# introAu.net
KiCad netlist of a schematic drawn in EAGLE
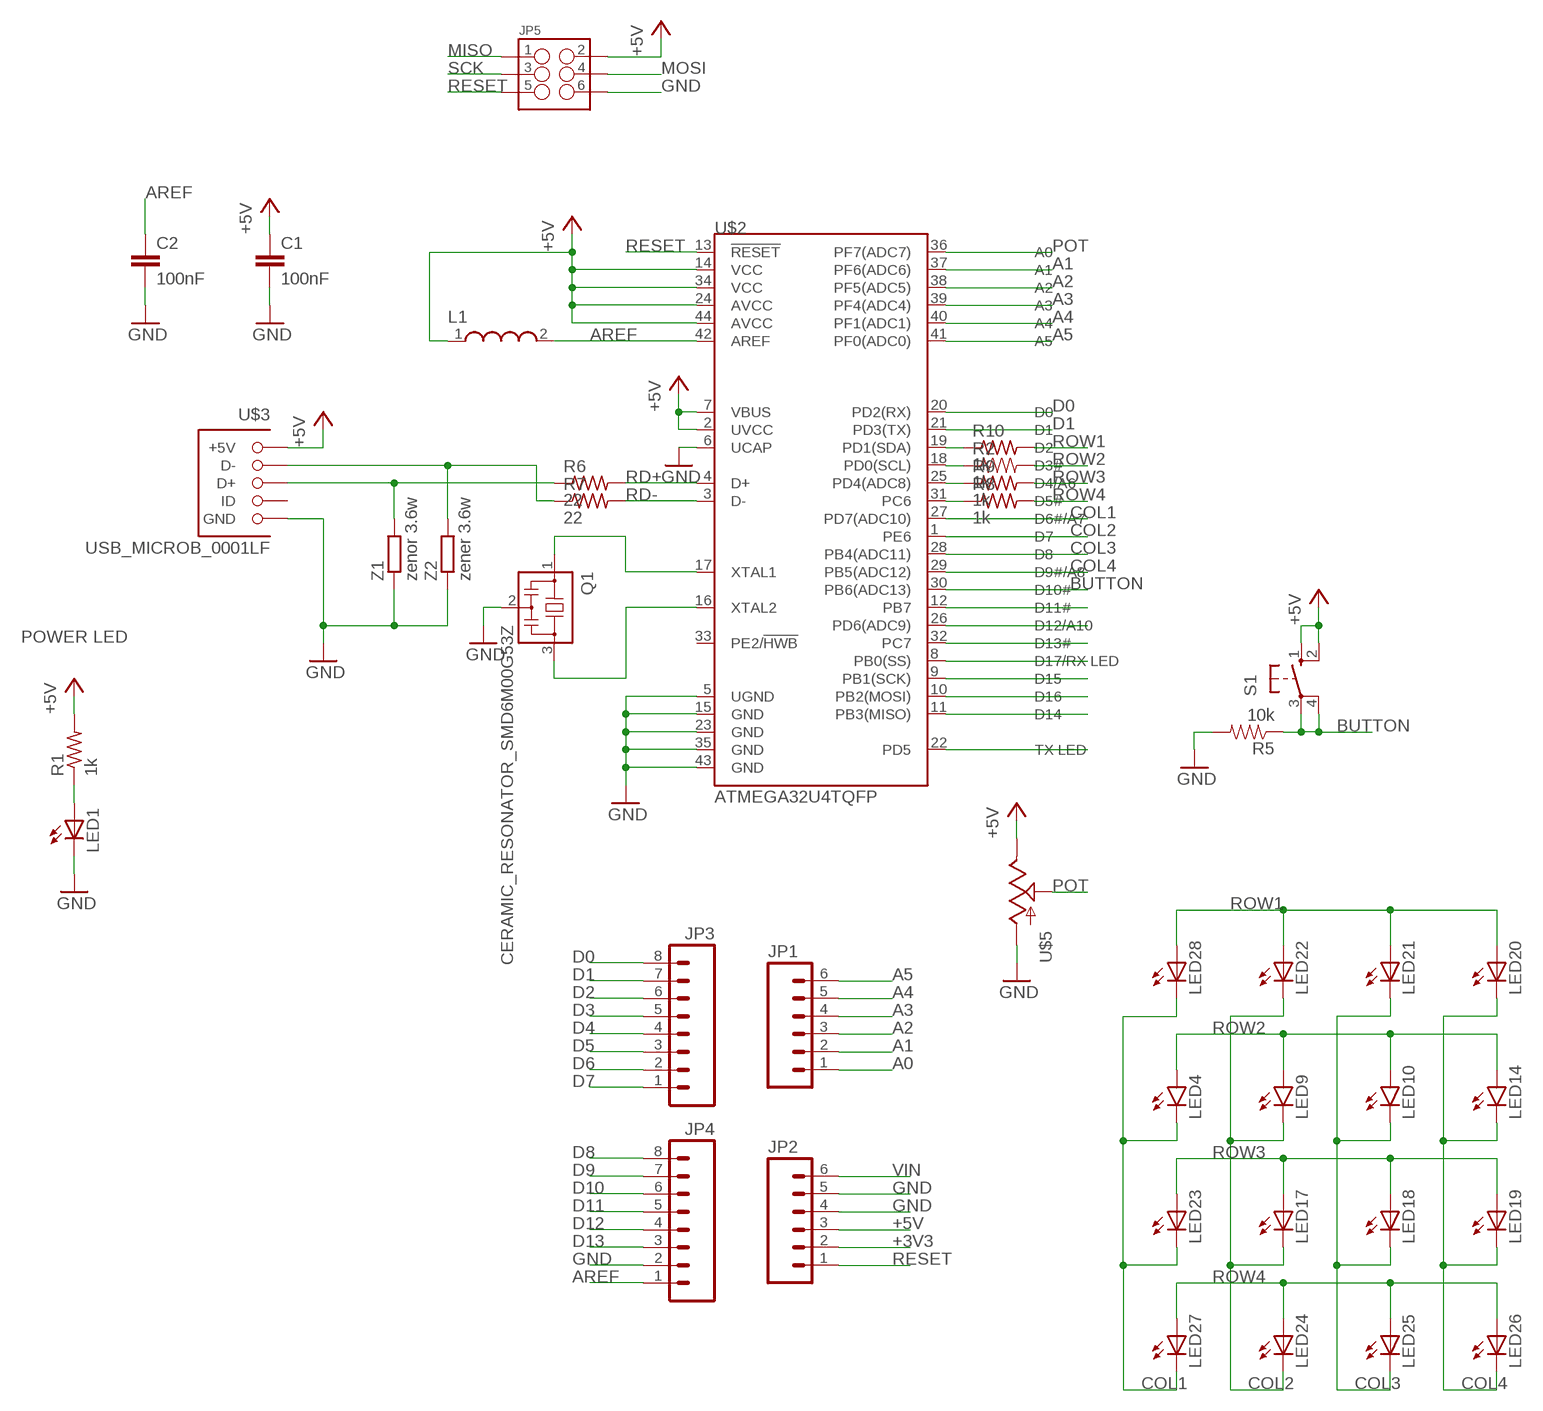
[diagram p0: schematic, sheet 1]

(export (version "E")
  (design (tool "Eeschema 10.0.6"))
  (components
    (comp (ref "C1")
      (value "100nF")
      (footprint "eagle-import:C0805")
      (libsource (lib "eagle-import") (part "C-EUC0805"))
    )
    (comp (ref "C2")
      (value "100nF")
      (footprint "eagle-import:C0805")
      (libsource (lib "eagle-import") (part "C-EUC0805"))
    )
    (comp (ref "JP1")
      (value "M06SMD-STRAIGHT-COMBO")
      (footprint "eagle-import:1X06_SMD_STRAIGHT_COMBO")
      (libsource (lib "eagle-import") (part "M06SMD-STRAIGHT-COMBO"))
    )
    (comp (ref "JP2")
      (value "M06SMD-STRAIGHT-COMBO")
      (footprint "eagle-import:1X06_SMD_STRAIGHT_COMBO")
      (libsource (lib "eagle-import") (part "M06SMD-STRAIGHT-COMBO"))
    )
    (comp (ref "JP3")
      (value "M08SMD-COMBO")
      (footprint "eagle-import:1X08_SMD_COMBINED")
      (libsource (lib "eagle-import") (part "M08SMD-COMBO"))
    )
    (comp (ref "JP4")
      (value "M08SMD-COMBO")
      (footprint "eagle-import:1X08_SMD_COMBINED")
      (libsource (lib "eagle-import") (part "M08SMD-COMBO"))
    )
    (comp (ref "JP5")
      (value "M03X22X3_SILK_SM")
      (footprint "eagle-import:2X3")
      (libsource (lib "eagle-import") (part "M03X22X3_SILK_SM"))
    )
    (comp (ref "L1")
      (value "WE-CBF_0805(WB/HS)")
      (footprint "eagle-import:WE-CBF_0805(W=3.0)")
      (libsource (lib "eagle-import") (part "WE-CBF_0805(WB/HS)"))
    )
    (comp (ref "LED1")
      (value "LEDCHIPLED_0805")
      (footprint "eagle-import:CHIPLED_0805")
      (libsource (lib "eagle-import") (part "LEDCHIPLED_0805"))
    )
    (comp (ref "LED4")
      (value "LED5MM")
      (footprint "eagle-import:LED5MM")
      (libsource (lib "eagle-import") (part "LED5MM"))
    )
    (comp (ref "LED9")
      (value "LED5MM")
      (footprint "eagle-import:LED5MM")
      (libsource (lib "eagle-import") (part "LED5MM"))
    )
    (comp (ref "LED10")
      (value "LED5MM")
      (footprint "eagle-import:LED5MM")
      (libsource (lib "eagle-import") (part "LED5MM"))
    )
    (comp (ref "LED14")
      (value "LED5MM")
      (footprint "eagle-import:LED5MM")
      (libsource (lib "eagle-import") (part "LED5MM"))
    )
    (comp (ref "LED17")
      (value "LEDCHIPLED_0805")
      (footprint "eagle-import:CHIPLED_0805")
      (libsource (lib "eagle-import") (part "LEDCHIPLED_0805"))
    )
    (comp (ref "LED18")
      (value "LEDCHIPLED_0805")
      (footprint "eagle-import:CHIPLED_0805")
      (libsource (lib "eagle-import") (part "LEDCHIPLED_0805"))
    )
    (comp (ref "LED19")
      (value "LEDCHIPLED_0805")
      (footprint "eagle-import:CHIPLED_0805")
      (libsource (lib "eagle-import") (part "LEDCHIPLED_0805"))
    )
    (comp (ref "LED20")
      (value "LEDCHIPLED_0805")
      (footprint "eagle-import:CHIPLED_0805")
      (libsource (lib "eagle-import") (part "LEDCHIPLED_0805"))
    )
    (comp (ref "LED21")
      (value "LEDCHIPLED_0805")
      (footprint "eagle-import:CHIPLED_0805")
      (libsource (lib "eagle-import") (part "LEDCHIPLED_0805"))
    )
    (comp (ref "LED22")
      (value "LEDCHIPLED_0805")
      (footprint "eagle-import:CHIPLED_0805")
      (libsource (lib "eagle-import") (part "LEDCHIPLED_0805"))
    )
    (comp (ref "LED23")
      (value "LEDCHIPLED_0805")
      (footprint "eagle-import:CHIPLED_0805")
      (libsource (lib "eagle-import") (part "LEDCHIPLED_0805"))
    )
    (comp (ref "LED24")
      (value "LEDCHIPLED_0805")
      (footprint "eagle-import:CHIPLED_0805")
      (libsource (lib "eagle-import") (part "LEDCHIPLED_0805"))
    )
    (comp (ref "LED25")
      (value "LEDCHIPLED_0805")
      (footprint "eagle-import:CHIPLED_0805")
      (libsource (lib "eagle-import") (part "LEDCHIPLED_0805"))
    )
    (comp (ref "LED26")
      (value "LEDCHIPLED_0805")
      (footprint "eagle-import:CHIPLED_0805")
      (libsource (lib "eagle-import") (part "LEDCHIPLED_0805"))
    )
    (comp (ref "LED27")
      (value "LEDCHIPLED_0805")
      (footprint "eagle-import:CHIPLED_0805")
      (libsource (lib "eagle-import") (part "LEDCHIPLED_0805"))
    )
    (comp (ref "LED28")
      (value "LEDCHIPLED_0805")
      (footprint "eagle-import:CHIPLED_0805")
      (libsource (lib "eagle-import") (part "LEDCHIPLED_0805"))
    )
    (comp (ref "Q1")
      (value "CERAMIC_RESONATOR_SMD6M00G53Z")
      (footprint "eagle-import:CERAMIC_RESONATOR_SMD")
      (fields (field (name "MPN") "CSTCR6M00G53-R0"))
      (libsource (lib "eagle-import") (part "CERAMIC_RESONATOR_SMD6M00G53Z"))
    )
    (comp (ref "R1")
      (value "1k")
      (footprint "eagle-import:R0805")
      (libsource (lib "eagle-import") (part "R-US_R0805"))
    )
    (comp (ref "R2")
      (value "1k")
      (footprint "eagle-import:AXIAL-0.3EZ")
      (libsource (lib "eagle-import") (part "1KOHM1/4W5%(PTH)HORIZ-KIT"))
    )
    (comp (ref "R5")
      (value "10k")
      (footprint "eagle-import:AXIAL-0.3EZ")
      (libsource (lib "eagle-import") (part "1KOHM1/4W5%(PTH)HORIZ-KIT"))
    )
    (comp (ref "R6")
      (value "22")
      (footprint "eagle-import:R0805")
      (libsource (lib "eagle-import") (part "R-US_R0805"))
    )
    (comp (ref "R7")
      (value "22")
      (footprint "eagle-import:R0805")
      (libsource (lib "eagle-import") (part "R-US_R0805"))
    )
    (comp (ref "R8")
      (value "1k")
      (footprint "eagle-import:R0805")
      (libsource (lib "eagle-import") (part "R-US_R0805"))
    )
    (comp (ref "R9")
      (value "1k")
      (footprint "eagle-import:R0805")
      (libsource (lib "eagle-import") (part "R-US_R0805"))
    )
    (comp (ref "R10")
      (value "1k")
      (footprint "eagle-import:R0805")
      (libsource (lib "eagle-import") (part "R-US_R0805"))
    )
    (comp (ref "S1")
      (value "TACT_BUTTON")
      (footprint "eagle-import:B3F-10XX")
      (fields (field (name "MPN") "B3F-1000"))
      (libsource (lib "eagle-import") (part "TACT_BUTTON"))
    )
    (comp (ref "U$2")
      (value "ATMEGA32U4TQFP")
      (footprint "eagle-import:SPARKFUN-DIGITALIC_TQFP44")
      (libsource (lib "eagle-import") (part "ATMEGA32U4TQFP"))
    )
    (comp (ref "U$3")
      (value "USB_MICROB_0001LF")
      (footprint "eagle-import:USB_MICROB_CHEAPER")
      (libsource (lib "eagle-import") (part "USB_MICROB_0001LF"))
    )
    (comp (ref "U$5")
      (value "POT")
      (footprint "eagle-import:ALPS_POT")
      (libsource (lib "eagle-import") (part "POT"))
    )
    (comp (ref "Z1")
      (value "zenor 3.6w")
      (footprint "eagle-import:R0603")
      (libsource (lib "eagle-import") (part "R-EU_R0603"))
    )
    (comp (ref "Z2")
      (value "zener 3.6w")
      (footprint "eagle-import:R0603")
      (libsource (lib "eagle-import") (part "R-EU_R0603"))
    )
  )
  (nets
    (net (code "1") (name "+5V") (class "Default")
      (node (ref "C1") (pin "1") (pinfunction "1_1") (pintype "passive"))
      (node (ref "JP2") (pin "3") (pinfunction "3_3") (pintype "passive"))
      (node (ref "JP5") (pin "2") (pinfunction "2_2") (pintype "bidirectional"))
      (node (ref "L1") (pin "1") (pinfunction "1_1") (pintype "passive"))
      (node (ref "R1") (pin "2") (pinfunction "2_2") (pintype "passive"))
      (node (ref "S1") (pin "1") (pinfunction "S_1") (pintype "passive"))
      (node (ref "S1") (pin "2") (pinfunction "S1_2") (pintype "passive"))
      (node (ref "U$2") (pin "14") (pinfunction "VCC_14") (pintype "bidirectional"))
      (node (ref "U$2") (pin "2") (pinfunction "UVCC_2") (pintype "bidirectional"))
      (node (ref "U$2") (pin "24") (pinfunction "AVCC_24") (pintype "bidirectional"))
      (node (ref "U$2") (pin "34") (pinfunction "VCC_34") (pintype "bidirectional"))
      (node (ref "U$2") (pin "44") (pinfunction "AVCC_44") (pintype "bidirectional"))
      (node (ref "U$2") (pin "7") (pinfunction "VBUS_7") (pintype "bidirectional"))
      (node (ref "U$3") (pin "P$1") (pinfunction "+5V_P$1") (pintype "bidirectional"))
      (node (ref "U$5") (pin "P$1") (pinfunction "E_P$1") (pintype "passive"))
    )
    (net (code "2") (name "/+3V3") (class "Default")
      (node (ref "JP2") (pin "2") (pinfunction "2_2") (pintype "passive"))
    )
    (net (code "3") (name "/A0") (class "Default")
      (node (ref "JP1") (pin "1") (pinfunction "1_1") (pintype "passive"))
    )
    (net (code "4") (name "/A1") (class "Default")
      (node (ref "JP1") (pin "2") (pinfunction "2_2") (pintype "passive"))
      (node (ref "U$2") (pin "37") (pinfunction "PF6(ADC6)_37") (pintype "bidirectional"))
    )
    (net (code "5") (name "/A2") (class "Default")
      (node (ref "JP1") (pin "3") (pinfunction "3_3") (pintype "passive"))
      (node (ref "U$2") (pin "38") (pinfunction "PF5(ADC5)_38") (pintype "bidirectional"))
    )
    (net (code "6") (name "/A3") (class "Default")
      (node (ref "JP1") (pin "4") (pinfunction "4_4") (pintype "passive"))
      (node (ref "U$2") (pin "39") (pinfunction "PF4(ADC4)_39") (pintype "bidirectional"))
    )
    (net (code "7") (name "/A4") (class "Default")
      (node (ref "JP1") (pin "5") (pinfunction "5_5") (pintype "passive"))
      (node (ref "U$2") (pin "40") (pinfunction "PF1(ADC1)_40") (pintype "bidirectional"))
    )
    (net (code "8") (name "/A5") (class "Default")
      (node (ref "JP1") (pin "6") (pinfunction "6_6") (pintype "passive"))
      (node (ref "U$2") (pin "41") (pinfunction "PF0(ADC0)_41") (pintype "bidirectional"))
    )
    (net (code "9") (name "/AREF") (class "Default")
      (node (ref "C2") (pin "1") (pinfunction "1_1") (pintype "passive"))
      (node (ref "JP4") (pin "1") (pinfunction "1_1") (pintype "passive"))
      (node (ref "L1") (pin "2") (pinfunction "2_2") (pintype "passive"))
      (node (ref "U$2") (pin "42") (pinfunction "AREF_42") (pintype "bidirectional"))
    )
    (net (code "10") (name "/BUTTON") (class "Default")
      (node (ref "R5") (pin "P$1") (pinfunction "1_P$1") (pintype "passive"))
      (node (ref "S1") (pin "3") (pinfunction "P_3") (pintype "passive"))
      (node (ref "S1") (pin "4") (pinfunction "P1_4") (pintype "passive"))
      (node (ref "U$2") (pin "30") (pinfunction "PB6(ADC13)_30") (pintype "bidirectional"))
    )
    (net (code "11") (name "/COL1") (class "Default")
      (node (ref "LED23") (pin "C") (pinfunction "C_C") (pintype "passive"))
      (node (ref "LED27") (pin "C") (pinfunction "C_C") (pintype "passive"))
      (node (ref "LED28") (pin "C") (pinfunction "C_C") (pintype "passive"))
      (node (ref "LED4") (pin "K") (pinfunction "C_K") (pintype "passive"))
      (node (ref "U$2") (pin "27") (pinfunction "PD7(ADC10)_27") (pintype "bidirectional"))
    )
    (net (code "12") (name "/COL2") (class "Default")
      (node (ref "LED17") (pin "C") (pinfunction "C_C") (pintype "passive"))
      (node (ref "LED22") (pin "C") (pinfunction "C_C") (pintype "passive"))
      (node (ref "LED24") (pin "C") (pinfunction "C_C") (pintype "passive"))
      (node (ref "LED9") (pin "K") (pinfunction "C_K") (pintype "passive"))
      (node (ref "U$2") (pin "1") (pinfunction "PE6_1") (pintype "bidirectional"))
    )
    (net (code "13") (name "/COL3") (class "Default")
      (node (ref "LED10") (pin "K") (pinfunction "C_K") (pintype "passive"))
      (node (ref "LED18") (pin "C") (pinfunction "C_C") (pintype "passive"))
      (node (ref "LED21") (pin "C") (pinfunction "C_C") (pintype "passive"))
      (node (ref "LED25") (pin "C") (pinfunction "C_C") (pintype "passive"))
      (node (ref "U$2") (pin "28") (pinfunction "PB4(ADC11)_28") (pintype "bidirectional"))
    )
    (net (code "14") (name "/COL4") (class "Default")
      (node (ref "LED14") (pin "K") (pinfunction "C_K") (pintype "passive"))
      (node (ref "LED19") (pin "C") (pinfunction "C_C") (pintype "passive"))
      (node (ref "LED20") (pin "C") (pinfunction "C_C") (pintype "passive"))
      (node (ref "LED26") (pin "C") (pinfunction "C_C") (pintype "passive"))
      (node (ref "U$2") (pin "29") (pinfunction "PB5(ADC12)_29") (pintype "bidirectional"))
    )
    (net (code "15") (name "/D0") (class "Default")
      (node (ref "JP3") (pin "8") (pinfunction "8_8") (pintype "passive"))
      (node (ref "U$2") (pin "20") (pinfunction "PD2(RX)_20") (pintype "bidirectional"))
    )
    (net (code "16") (name "/D1") (class "Default")
      (node (ref "JP3") (pin "7") (pinfunction "7_7") (pintype "passive"))
      (node (ref "U$2") (pin "21") (pinfunction "PD3(TX)_21") (pintype "bidirectional"))
    )
    (net (code "17") (name "/D2") (class "Default")
      (node (ref "JP3") (pin "6") (pinfunction "6_6") (pintype "passive"))
    )
    (net (code "18") (name "/D3") (class "Default")
      (node (ref "JP3") (pin "5") (pinfunction "5_5") (pintype "passive"))
    )
    (net (code "19") (name "/D4") (class "Default")
      (node (ref "JP3") (pin "4") (pinfunction "4_4") (pintype "passive"))
    )
    (net (code "20") (name "/D5") (class "Default")
      (node (ref "JP3") (pin "3") (pinfunction "3_3") (pintype "passive"))
    )
    (net (code "21") (name "/D6") (class "Default")
      (node (ref "JP3") (pin "2") (pinfunction "2_2") (pintype "passive"))
    )
    (net (code "22") (name "/D7") (class "Default")
      (node (ref "JP3") (pin "1") (pinfunction "1_1") (pintype "passive"))
    )
    (net (code "23") (name "/D8") (class "Default")
      (node (ref "JP4") (pin "8") (pinfunction "8_8") (pintype "passive"))
    )
    (net (code "24") (name "/D9") (class "Default")
      (node (ref "JP4") (pin "7") (pinfunction "7_7") (pintype "passive"))
    )
    (net (code "25") (name "/D10") (class "Default")
      (node (ref "JP4") (pin "6") (pinfunction "6_6") (pintype "passive"))
    )
    (net (code "26") (name "/D11") (class "Default")
      (node (ref "JP4") (pin "5") (pinfunction "5_5") (pintype "passive"))
      (node (ref "U$2") (pin "12") (pinfunction "PB7_12") (pintype "bidirectional"))
    )
    (net (code "27") (name "/D12") (class "Default")
      (node (ref "JP4") (pin "4") (pinfunction "4_4") (pintype "passive"))
      (node (ref "U$2") (pin "26") (pinfunction "PD6(ADC9)_26") (pintype "bidirectional"))
    )
    (net (code "28") (name "/D13") (class "Default")
      (node (ref "JP4") (pin "3") (pinfunction "3_3") (pintype "passive"))
      (node (ref "U$2") (pin "32") (pinfunction "PC7_32") (pintype "bidirectional"))
    )
    (net (code "29") (name "/MISO") (class "Default")
      (node (ref "JP5") (pin "1") (pinfunction "1_1") (pintype "bidirectional"))
    )
    (net (code "30") (name "/MOSI") (class "Default")
      (node (ref "JP5") (pin "4") (pinfunction "4_4") (pintype "bidirectional"))
    )
    (net (code "31") (name "/POT") (class "Default")
      (node (ref "U$2") (pin "36") (pinfunction "PF7(ADC7)_36") (pintype "bidirectional"))
      (node (ref "U$5") (pin "P$2") (pinfunction "S_P$2") (pintype "passive"))
    )
    (net (code "32") (name "/RD+") (class "Default")
      (node (ref "R6") (pin "2") (pinfunction "2_2") (pintype "passive"))
      (node (ref "U$2") (pin "4") (pinfunction "D+_4") (pintype "bidirectional"))
    )
    (net (code "33") (name "/RD-") (class "Default")
      (node (ref "R7") (pin "2") (pinfunction "2_2") (pintype "passive"))
      (node (ref "U$2") (pin "3") (pinfunction "D-_3") (pintype "bidirectional"))
    )
    (net (code "34") (name "/RESET") (class "Default")
      (node (ref "JP2") (pin "1") (pinfunction "1_1") (pintype "passive"))
      (node (ref "JP5") (pin "5") (pinfunction "5_5") (pintype "bidirectional"))
      (node (ref "U$2") (pin "13") (pinfunction "~{RESET}_13") (pintype "bidirectional"))
    )
    (net (code "35") (name "/ROW1") (class "Default")
      (node (ref "LED20") (pin "A") (pinfunction "A_A") (pintype "passive"))
      (node (ref "LED21") (pin "A") (pinfunction "A_A") (pintype "passive"))
      (node (ref "LED22") (pin "A") (pinfunction "A_A") (pintype "passive"))
      (node (ref "LED28") (pin "A") (pinfunction "A_A") (pintype "passive"))
      (node (ref "R10") (pin "2") (pinfunction "2_2") (pintype "passive"))
    )
    (net (code "36") (name "/ROW2") (class "Default")
      (node (ref "LED10") (pin "A") (pinfunction "A_A") (pintype "passive"))
      (node (ref "LED14") (pin "A") (pinfunction "A_A") (pintype "passive"))
      (node (ref "LED4") (pin "A") (pinfunction "A_A") (pintype "passive"))
      (node (ref "LED9") (pin "A") (pinfunction "A_A") (pintype "passive"))
      (node (ref "R2") (pin "P$2") (pinfunction "2_P$2") (pintype "passive"))
    )
    (net (code "37") (name "/ROW3") (class "Default")
      (node (ref "LED17") (pin "A") (pinfunction "A_A") (pintype "passive"))
      (node (ref "LED18") (pin "A") (pinfunction "A_A") (pintype "passive"))
      (node (ref "LED19") (pin "A") (pinfunction "A_A") (pintype "passive"))
      (node (ref "LED23") (pin "A") (pinfunction "A_A") (pintype "passive"))
      (node (ref "R9") (pin "2") (pinfunction "2_2") (pintype "passive"))
    )
    (net (code "38") (name "/ROW4") (class "Default")
      (node (ref "LED24") (pin "A") (pinfunction "A_A") (pintype "passive"))
      (node (ref "LED25") (pin "A") (pinfunction "A_A") (pintype "passive"))
      (node (ref "LED26") (pin "A") (pinfunction "A_A") (pintype "passive"))
      (node (ref "LED27") (pin "A") (pinfunction "A_A") (pintype "passive"))
      (node (ref "R8") (pin "2") (pinfunction "2_2") (pintype "passive"))
    )
    (net (code "39") (name "/SCK") (class "Default")
      (node (ref "JP5") (pin "3") (pinfunction "3_3") (pintype "bidirectional"))
    )
    (net (code "40") (name "/VIN") (class "Default")
      (node (ref "JP2") (pin "6") (pinfunction "6_6") (pintype "passive"))
    )
    (net (code "41") (name "GND") (class "Default")
      (node (ref "C1") (pin "2") (pinfunction "2_2") (pintype "passive"))
      (node (ref "C2") (pin "2") (pinfunction "2_2") (pintype "passive"))
      (node (ref "JP2") (pin "4") (pinfunction "4_4") (pintype "passive"))
      (node (ref "JP2") (pin "5") (pinfunction "5_5") (pintype "passive"))
      (node (ref "JP4") (pin "2") (pinfunction "2_2") (pintype "passive"))
      (node (ref "JP5") (pin "6") (pinfunction "6_6") (pintype "bidirectional"))
      (node (ref "LED1") (pin "C") (pinfunction "C_C") (pintype "passive"))
      (node (ref "Q1") (pin "2") (pinfunction "2_2") (pintype "passive"))
      (node (ref "R5") (pin "P$2") (pinfunction "2_P$2") (pintype "passive"))
      (node (ref "U$2") (pin "15") (pinfunction "GND_15") (pintype "bidirectional"))
      (node (ref "U$2") (pin "23") (pinfunction "GND_23") (pintype "bidirectional"))
      (node (ref "U$2") (pin "35") (pinfunction "GND_35") (pintype "bidirectional"))
      (node (ref "U$2") (pin "43") (pinfunction "GND_43") (pintype "bidirectional"))
      (node (ref "U$2") (pin "5") (pinfunction "UGND_5") (pintype "bidirectional"))
      (node (ref "U$2") (pin "6") (pinfunction "UCAP_6") (pintype "bidirectional"))
      (node (ref "U$3") (pin "P$4") (pinfunction "GND_P$4") (pintype "bidirectional"))
      (node (ref "U$5") (pin "P$3") (pinfunction "A_P$3") (pintype "passive"))
      (node (ref "Z1") (pin "1") (pinfunction "1_1") (pintype "passive"))
      (node (ref "Z2") (pin "1") (pinfunction "1_1") (pintype "passive"))
    )
    (net (code "42") (name "Net-(LED1-PadA)") (class "Default")
      (node (ref "LED1") (pin "A") (pinfunction "A_A") (pintype "passive"))
      (node (ref "R1") (pin "1") (pinfunction "1_1") (pintype "passive"))
    )
    (net (code "43") (name "Net-(R2-1)") (class "Default")
      (node (ref "R2") (pin "P$1") (pinfunction "1_P$1") (pintype "passive"))
      (node (ref "U$2") (pin "18") (pinfunction "PD0(SCL)_18") (pintype "bidirectional"))
    )
    (net (code "44") (name "Net-(U$2-PC6)") (class "Default")
      (node (ref "R8") (pin "1") (pinfunction "1_1") (pintype "passive"))
      (node (ref "U$2") (pin "31") (pinfunction "PC6_31") (pintype "bidirectional"))
    )
    (net (code "45") (name "Net-(U$2-PD1(SDA))") (class "Default")
      (node (ref "R10") (pin "1") (pinfunction "1_1") (pintype "passive"))
      (node (ref "U$2") (pin "19") (pinfunction "PD1(SDA)_19") (pintype "bidirectional"))
    )
    (net (code "46") (name "Net-(U$2-PD4(ADC8))") (class "Default")
      (node (ref "R9") (pin "1") (pinfunction "1_1") (pintype "passive"))
      (node (ref "U$2") (pin "25") (pinfunction "PD4(ADC8)_25") (pintype "bidirectional"))
    )
    (net (code "47") (name "Net-(U$2-XTAL1)") (class "Default")
      (node (ref "Q1") (pin "1") (pinfunction "1_1") (pintype "passive"))
      (node (ref "U$2") (pin "17") (pinfunction "XTAL1_17") (pintype "bidirectional"))
    )
    (net (code "48") (name "Net-(U$2-XTAL2)") (class "Default")
      (node (ref "Q1") (pin "3") (pinfunction "3_3") (pintype "passive"))
      (node (ref "U$2") (pin "16") (pinfunction "XTAL2_16") (pintype "bidirectional"))
    )
    (net (code "49") (name "Net-(U$3-D+)") (class "Default")
      (node (ref "R6") (pin "1") (pinfunction "1_1") (pintype "passive"))
      (node (ref "U$3") (pin "P$3") (pinfunction "D+_P$3") (pintype "bidirectional"))
      (node (ref "Z1") (pin "2") (pinfunction "2_2") (pintype "passive"))
    )
    (net (code "50") (name "Net-(U$3-D-)") (class "Default")
      (node (ref "R7") (pin "1") (pinfunction "1_1") (pintype "passive"))
      (node (ref "U$3") (pin "P$2") (pinfunction "D-_P$2") (pintype "bidirectional"))
      (node (ref "Z2") (pin "2") (pinfunction "2_2") (pintype "passive"))
    )
    (net (code "51") (name "unconnected-(U$2-PB0(SS)-Pad8)") (class "Default")
      (node (ref "U$2") (pin "8") (pinfunction "PB0(SS)_8") (pintype "bidirectional"))
    )
    (net (code "52") (name "unconnected-(U$2-PB1(SCK)-Pad9)") (class "Default")
      (node (ref "U$2") (pin "9") (pinfunction "PB1(SCK)_9") (pintype "bidirectional"))
    )
    (net (code "53") (name "unconnected-(U$2-PB2(MOSI)-Pad10)") (class "Default")
      (node (ref "U$2") (pin "10") (pinfunction "PB2(MOSI)_10") (pintype "bidirectional"))
    )
    (net (code "54") (name "unconnected-(U$2-PB3(MISO)-Pad11)") (class "Default")
      (node (ref "U$2") (pin "11") (pinfunction "PB3(MISO)_11") (pintype "bidirectional"))
    )
    (net (code "55") (name "unconnected-(U$2-PD5-Pad22)") (class "Default")
      (node (ref "U$2") (pin "22") (pinfunction "PD5_22") (pintype "bidirectional"))
    )
    (net (code "56") (name "unconnected-(U$2-PE2{slash}~{HWB}-Pad33)") (class "Default")
      (node (ref "U$2") (pin "33") (pinfunction "PE2/~{HWB}_33") (pintype "bidirectional"))
    )
    (net (code "57") (name "unconnected-(U$3-ID-PadP$5)") (class "Default")
      (node (ref "U$3") (pin "P$5") (pinfunction "ID_P$5") (pintype "bidirectional"))
    )
  )
)
